# FPGA_programming.net
KiCad netlist of a schematic drawn in Altium Designer
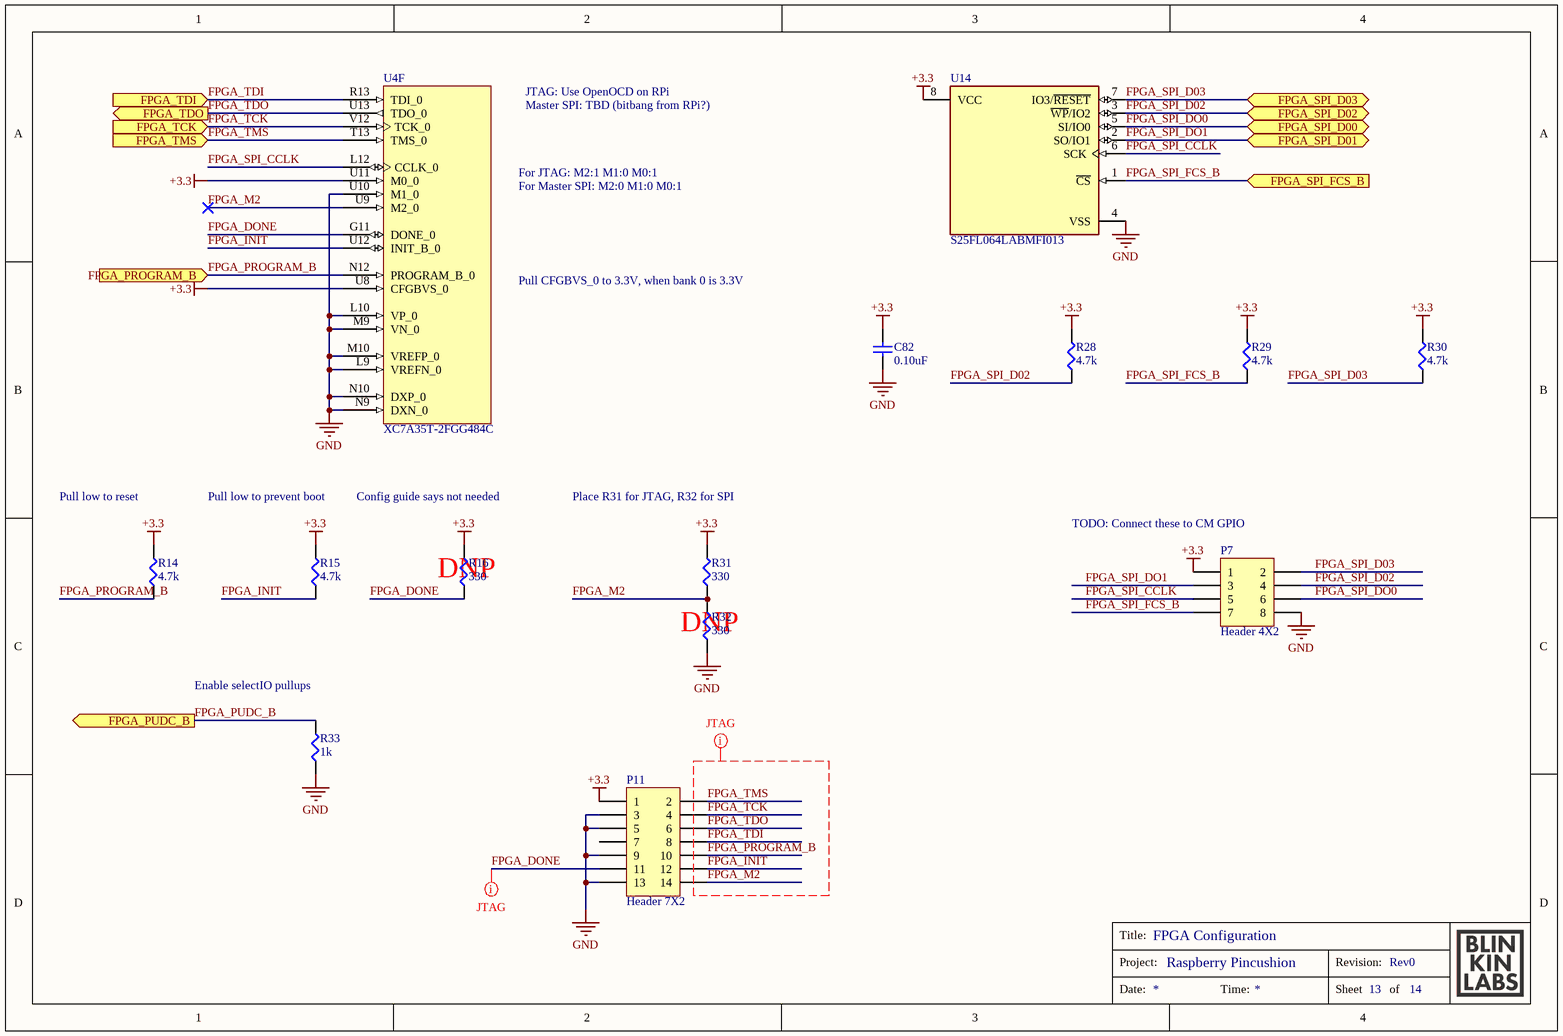
[diagram p0: FPGA programming.SchDoc]

(export (version "E")
  (design (tool "Eeschema 10.0.6"))
  (components
    (comp (ref "C82")
      (value "0.10uF")
      (footprint "CAPC1005X06L")
      (description "CAP CER 0.1UF 10V X5R 0402")
      (fields
        (field (name "PARTNUMBER") "GRM155R61A104KA01D")
        (field (name "DIGI-KEY PART NUMBER") "490-1318-1-ND")
      )
      (libsource (lib "cap_murata") (part "CAPACITOR"))
    )
    (comp (ref "P7")
      (value "Header 4X2")
      (footprint "HDR2X4")
      (description "Header, 4-Pin, Dual row")
      (fields (field (name "PUBLISHER") "Altium Limited"))
      (libsource (lib "Miscellaneous Connectors") (part "Header 4X2"))
    )
    (comp (ref "P11")
      (value "Header 7X2")
      (footprint "HDR2X7")
      (description "Header, 7-Pin, Dual row")
      (fields (field (name "PUBLISHER") "Altium Limited"))
      (libsource (lib "Miscellaneous Connectors") (part "Header 7X2"))
    )
    (comp (ref "R14")
      (value "4.7k")
      (footprint "ERJ2G(0402)_L")
      (description "RES SMD 4.7K OHM 1% 1/5W 0402")
      (fields (field (name "PARTNUMBER") "ERJ-PA2F4701X") (field (name "DIGI-KEY PART NUMBER") "P17228CT-ND"))
      (libsource (lib "res_panasonic_erj_xls") (part "RESISTOR"))
    )
    (comp (ref "R15")
      (value "4.7k")
      (footprint "ERJ2G(0402)_L")
      (description "RES SMD 4.7K OHM 1% 1/5W 0402")
      (fields (field (name "PARTNUMBER") "ERJ-PA2F4701X") (field (name "DIGI-KEY PART NUMBER") "P17228CT-ND"))
      (libsource (lib "res_panasonic_erj_xls") (part "RESISTOR"))
    )
    (comp (ref "R16")
      (value "330")
      (footprint "ERJ2G(0402)_L")
      (description "RES SMD 330 OHM 1% 1/10W 0402")
      (fields (field (name "PARTNUMBER") "ERJ-2RKF3300X") (field (name "DIGI-KEY PART NUMBER") "P330LCT-ND"))
      (libsource (lib "res_panasonic_erj_xls") (part "RESISTOR"))
    )
    (comp (ref "R28")
      (value "4.7k")
      (footprint "ERJ2G(0402)_L")
      (description "RES SMD 4.7K OHM 1% 1/5W 0402")
      (fields (field (name "PARTNUMBER") "ERJ-PA2F4701X") (field (name "DIGI-KEY PART NUMBER") "P17228CT-ND"))
      (libsource (lib "res_panasonic_erj_xls") (part "RESISTOR"))
    )
    (comp (ref "R29")
      (value "4.7k")
      (footprint "ERJ2G(0402)_L")
      (description "RES SMD 4.7K OHM 1% 1/5W 0402")
      (fields (field (name "PARTNUMBER") "ERJ-PA2F4701X") (field (name "DIGI-KEY PART NUMBER") "P17228CT-ND"))
      (libsource (lib "res_panasonic_erj_xls") (part "RESISTOR"))
    )
    (comp (ref "R30")
      (value "4.7k")
      (footprint "ERJ2G(0402)_L")
      (description "RES SMD 4.7K OHM 1% 1/5W 0402")
      (fields (field (name "PARTNUMBER") "ERJ-PA2F4701X") (field (name "DIGI-KEY PART NUMBER") "P17228CT-ND"))
      (libsource (lib "res_panasonic_erj_xls") (part "RESISTOR"))
    )
    (comp (ref "R31")
      (value "330")
      (footprint "ERJ2G(0402)_L")
      (description "RES SMD 330 OHM 1% 1/10W 0402")
      (fields (field (name "PARTNUMBER") "ERJ-2RKF3300X") (field (name "DIGI-KEY PART NUMBER") "P330LCT-ND"))
      (libsource (lib "res_panasonic_erj_xls") (part "RESISTOR"))
    )
    (comp (ref "R32")
      (value "330")
      (footprint "ERJ2G(0402)_L")
      (description "RES SMD 330 OHM 1% 1/10W 0402")
      (fields (field (name "PARTNUMBER") "ERJ-2RKF3300X") (field (name "DIGI-KEY PART NUMBER") "P330LCT-ND"))
      (libsource (lib "res_panasonic_erj_xls") (part "RESISTOR"))
    )
    (comp (ref "R33")
      (value "1k")
      (footprint "ERJ2G(0402)_L")
      (description "RES SMD 1K OHM 1% 1/10W 0402")
      (fields
        (field (name "PARTNUMBER") "ERJ-2RKF1001X")
        (field (name "DIGI-KEY PART NUMBER") "P1.00KLCT-ND")
      )
      (libsource (lib "res_panasonic_erj_xls") (part "RESISTOR"))
    )
    (comp (ref "U4")
      (value "XC7A35T-2FGG484C")
      (footprint "FGG484")
      (description "Artix-7 FPGA, 250 User I/Os, 4 GTP, 484-Ball BGA, Speed Grade 2, Commercial Grade, Pb-Free")
      (fields (field (name "MANUFACTURER") "Xilinx"))
      (libsource (lib "Altium Content Vault") (part "XLNX-XC7A35T-FGG484"))
    )
    (comp (ref "U14")
      (value "S25FL064LABMFI013")
      (footprint "FP-002-15548-MFG")
      (description "IC FLASH 64M SPI 108MHZ 8SOIC")
      (fields
        (field (name "OCTOPART") "https://octopart.com/s25fl064labmfi013-cypress+semiconductor-81630477")
        (field (name "MANUFACTURER") "Cypress Semiconductor")
      )
      (libsource (lib "Altium Content Vault") (part "c4eaf2d6a9f4aac38062d0181b336fb"))
    )
  )
  (nets
    (net (code "1") (name "+3.3") (class "Default")
      (node (ref "C82") (pin "2") (pinfunction "2_2") (pintype "passive"))
      (node (ref "P11") (pin "1") (pinfunction "1_1") (pintype "passive"))
      (node (ref "P7") (pin "1") (pinfunction "1_1") (pintype "passive"))
      (node (ref "R14") (pin "2") (pinfunction "2_2") (pintype "passive"))
      (node (ref "R15") (pin "2") (pinfunction "2_2") (pintype "passive"))
      (node (ref "R16") (pin "2") (pinfunction "2_2") (pintype "passive"))
      (node (ref "R28") (pin "2") (pinfunction "2_2") (pintype "passive"))
      (node (ref "R29") (pin "2") (pinfunction "2_2") (pintype "passive"))
      (node (ref "R30") (pin "2") (pinfunction "2_2") (pintype "passive"))
      (node (ref "R31") (pin "2") (pinfunction "2_2") (pintype "passive"))
      (node (ref "U14") (pin "8") (pinfunction "VCC_8") (pintype "power_in"))
      (node (ref "U4") (pin "U11") (pinfunction "M0_0_U11") (pintype "input"))
      (node (ref "U4") (pin "U8") (pinfunction "CFGBVS_0_U8") (pintype "input"))
    )
    (net (code "2") (name "/FPGA_DONE") (class "Default")
      (node (ref "P11") (pin "11") (pinfunction "11_11") (pintype "passive"))
      (node (ref "R16") (pin "1") (pinfunction "1_1") (pintype "passive"))
      (node (ref "U4") (pin "G11") (pinfunction "DONE_0_G11") (pintype "bidirectional"))
    )
    (net (code "3") (name "/FPGA_INIT") (class "Default")
      (node (ref "P11") (pin "12") (pinfunction "12_12") (pintype "passive"))
      (node (ref "R15") (pin "1") (pinfunction "1_1") (pintype "passive"))
      (node (ref "U4") (pin "U12") (pinfunction "INIT_B_0_U12") (pintype "bidirectional"))
    )
    (net (code "4") (name "/FPGA_M2") (class "Default")
      (node (ref "P11") (pin "14") (pinfunction "14_14") (pintype "passive"))
      (node (ref "R31") (pin "1") (pinfunction "1_1") (pintype "passive"))
      (node (ref "R32") (pin "2") (pinfunction "2_2") (pintype "passive"))
      (node (ref "U4") (pin "U9") (pinfunction "M2_0_U9") (pintype "input"))
    )
    (net (code "5") (name "/FPGA_PROGRAM_B") (class "Default")
      (node (ref "P11") (pin "10") (pinfunction "10_10") (pintype "passive"))
      (node (ref "R14") (pin "1") (pinfunction "1_1") (pintype "passive"))
      (node (ref "U4") (pin "N12") (pinfunction "PROGRAM_B_0_N12") (pintype "input"))
    )
    (net (code "6") (name "/FPGA_PUDC_B") (class "Default")
      (node (ref "R33") (pin "2") (pinfunction "2_2") (pintype "passive"))
    )
    (net (code "7") (name "/FPGA_SPI_CCLK") (class "Default")
      (node (ref "P7") (pin "5") (pinfunction "5_5") (pintype "passive"))
      (node (ref "U14") (pin "6") (pinfunction "SCK_6") (pintype "input"))
      (node (ref "U4") (pin "L12") (pinfunction "CCLK_0_L12") (pintype "bidirectional"))
    )
    (net (code "8") (name "/FPGA_SPI_D02") (class "Default")
      (node (ref "P7") (pin "4") (pinfunction "4_4") (pintype "passive"))
      (node (ref "R28") (pin "1") (pinfunction "1_1") (pintype "passive"))
      (node (ref "U14") (pin "3") (pinfunction "~{WP}/IO2_3") (pintype "bidirectional"))
    )
    (net (code "9") (name "/FPGA_SPI_D03") (class "Default")
      (node (ref "P7") (pin "2") (pinfunction "2_2") (pintype "passive"))
      (node (ref "R30") (pin "1") (pinfunction "1_1") (pintype "passive"))
      (node (ref "U14") (pin "7") (pinfunction "IO3/~{RESET}_7") (pintype "bidirectional"))
    )
    (net (code "10") (name "/FPGA_SPI_DO0") (class "Default")
      (node (ref "P7") (pin "6") (pinfunction "6_6") (pintype "passive"))
      (node (ref "U14") (pin "5") (pinfunction "SI/IO0_5") (pintype "bidirectional"))
    )
    (net (code "11") (name "/FPGA_SPI_DO1") (class "Default")
      (node (ref "P7") (pin "3") (pinfunction "3_3") (pintype "passive"))
      (node (ref "U14") (pin "2") (pinfunction "SO/IO1_2") (pintype "bidirectional"))
    )
    (net (code "12") (name "/FPGA_SPI_FCS_B") (class "Default")
      (node (ref "P7") (pin "7") (pinfunction "7_7") (pintype "passive"))
      (node (ref "R29") (pin "1") (pinfunction "1_1") (pintype "passive"))
      (node (ref "U14") (pin "1") (pinfunction "~{CS}_1") (pintype "input"))
    )
    (net (code "13") (name "/FPGA_TCK") (class "Default")
      (node (ref "P11") (pin "4") (pinfunction "4_4") (pintype "passive"))
      (node (ref "U4") (pin "V12") (pinfunction "TCK_0_V12") (pintype "input"))
    )
    (net (code "14") (name "/FPGA_TDI") (class "Default")
      (node (ref "P11") (pin "8") (pinfunction "8_8") (pintype "passive"))
      (node (ref "U4") (pin "R13") (pinfunction "TDI_0_R13") (pintype "input"))
    )
    (net (code "15") (name "/FPGA_TDO") (class "Default")
      (node (ref "P11") (pin "6") (pinfunction "6_6") (pintype "passive"))
      (node (ref "U4") (pin "U13") (pinfunction "TDO_0_U13") (pintype "output"))
    )
    (net (code "16") (name "/FPGA_TMS") (class "Default")
      (node (ref "P11") (pin "2") (pinfunction "2_2") (pintype "passive"))
      (node (ref "U4") (pin "T13") (pinfunction "TMS_0_T13") (pintype "input"))
    )
    (net (code "17") (name "GND") (class "Default")
      (node (ref "C82") (pin "1") (pinfunction "1_1") (pintype "passive"))
      (node (ref "P11") (pin "13") (pinfunction "13_13") (pintype "passive"))
      (node (ref "P11") (pin "3") (pinfunction "3_3") (pintype "passive"))
      (node (ref "P11") (pin "5") (pinfunction "5_5") (pintype "passive"))
      (node (ref "P11") (pin "9") (pinfunction "9_9") (pintype "passive"))
      (node (ref "P7") (pin "8") (pinfunction "8_8") (pintype "passive"))
      (node (ref "R32") (pin "1") (pinfunction "1_1") (pintype "passive"))
      (node (ref "R33") (pin "1") (pinfunction "1_1") (pintype "passive"))
      (node (ref "U14") (pin "4") (pinfunction "VSS_4") (pintype "power_in"))
      (node (ref "U4") (pin "L10") (pinfunction "VP_0_L10") (pintype "input"))
      (node (ref "U4") (pin "L9") (pinfunction "VREFN_0_L9") (pintype "input"))
      (node (ref "U4") (pin "M10") (pinfunction "VREFP_0_M10") (pintype "input"))
      (node (ref "U4") (pin "M9") (pinfunction "VN_0_M9") (pintype "input"))
      (node (ref "U4") (pin "N10") (pinfunction "DXP_0_N10") (pintype "input"))
      (node (ref "U4") (pin "N9") (pinfunction "DXN_0_N9") (pintype "input"))
      (node (ref "U4") (pin "U10") (pinfunction "M1_0_U10") (pintype "input"))
    )
    (net (code "18") (name "unconnected-(P11-Pad7)") (class "Default")
      (node (ref "P11") (pin "7") (pinfunction "7_7") (pintype "passive"))
    )
  )
)
